# alphanewt_v1_6.net
KiCad netlist of a schematic drawn in EAGLE
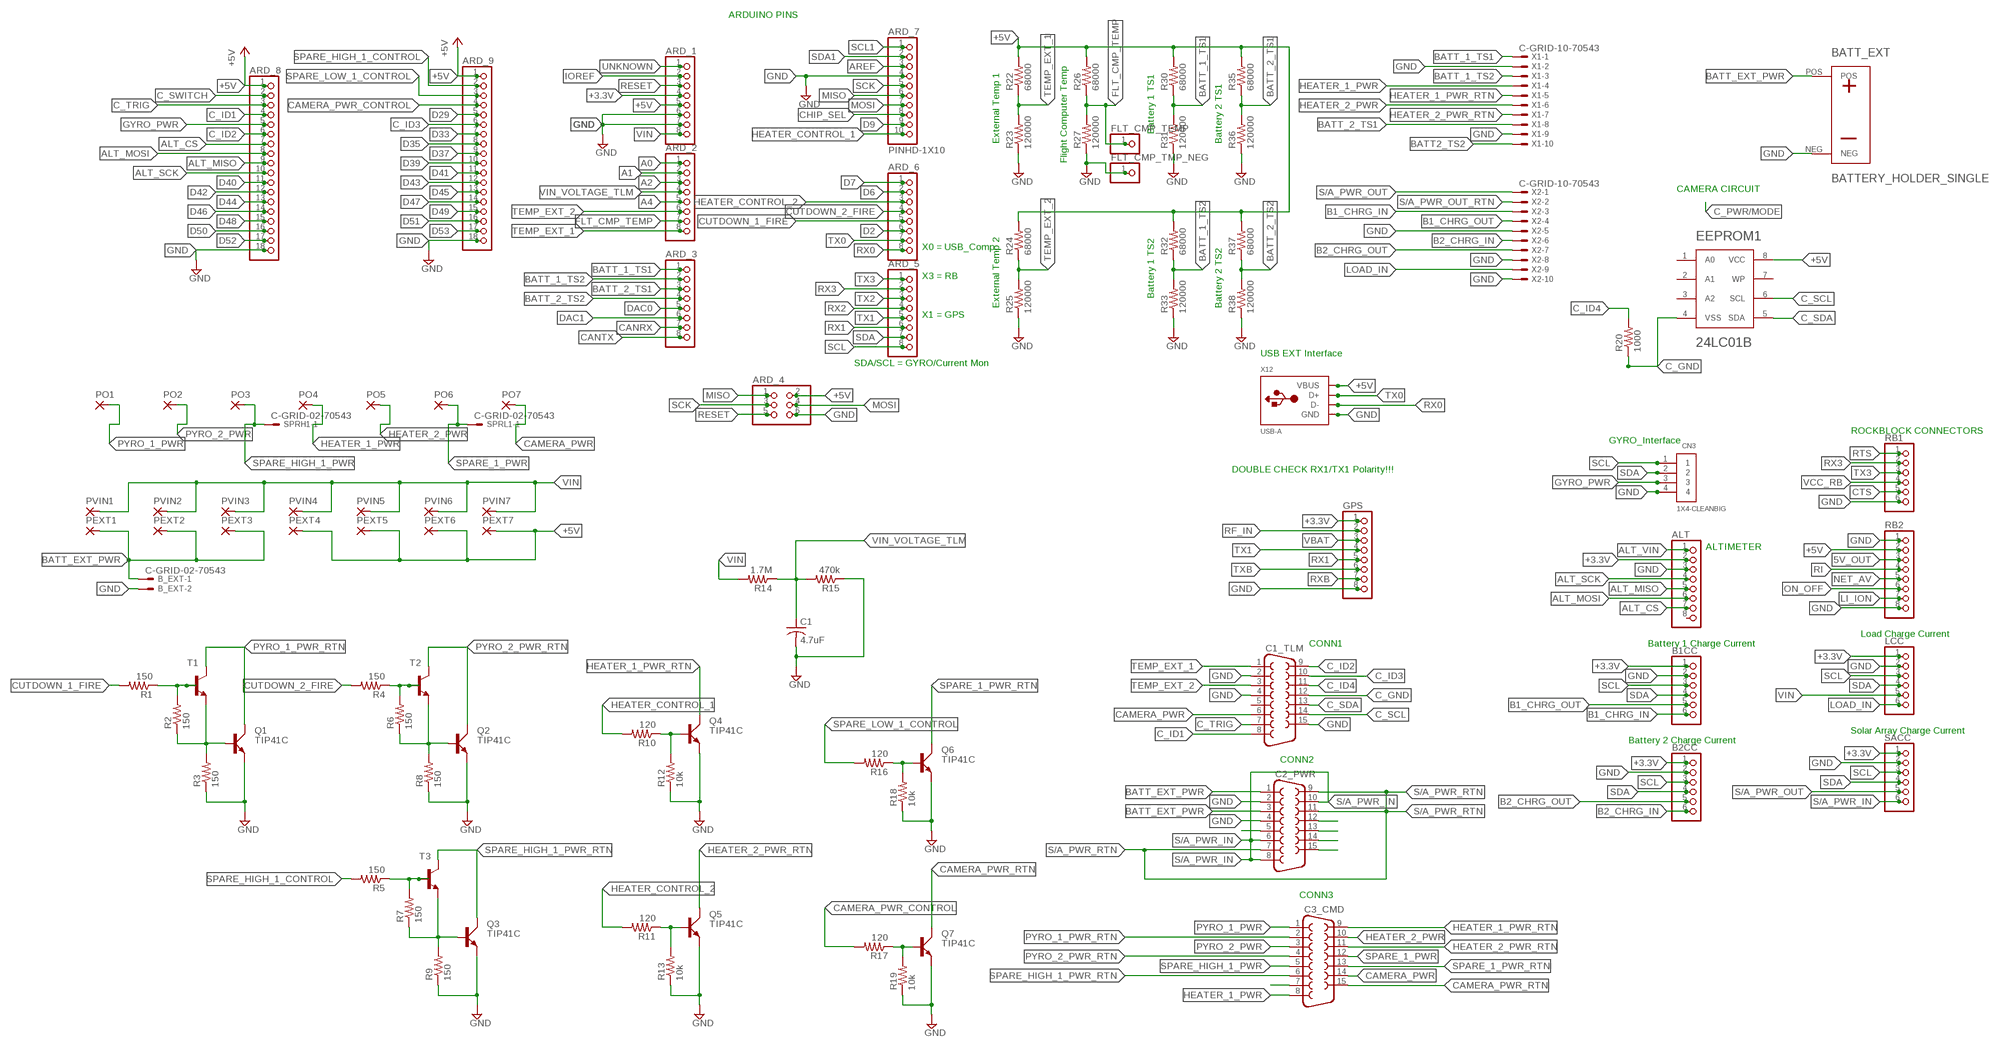
[diagram p0: schematic, sheet 1]

(export (version "E")
  (design (tool "Eeschema 10.0.6"))
  (components
    (comp (ref "ALT")
      (value "PINHD-1X8BIG")
      (footprint "eagle-import:1X08-BIG")
      (libsource (lib "eagle-import") (part "PINHD-1X8BIG"))
    )
    (comp (ref "ARD_1")
      (value "PINHD-1X8BIG")
      (footprint "eagle-import:1X08-BIG")
      (libsource (lib "eagle-import") (part "PINHD-1X8BIG"))
    )
    (comp (ref "ARD_2")
      (value "PINHD-1X8BIG")
      (footprint "eagle-import:1X08-BIG")
      (libsource (lib "eagle-import") (part "PINHD-1X8BIG"))
    )
    (comp (ref "ARD_3")
      (value "PINHD-1X8BIG")
      (footprint "eagle-import:1X08-BIG")
      (libsource (lib "eagle-import") (part "PINHD-1X8BIG"))
    )
    (comp (ref "ARD_4")
      (value "PINHD-2X3")
      (footprint "eagle-import:2X03")
      (libsource (lib "eagle-import") (part "PINHD-2X3"))
    )
    (comp (ref "ARD_5")
      (value "PINHD-1X8BIG")
      (footprint "eagle-import:1X08-BIG")
      (libsource (lib "eagle-import") (part "PINHD-1X8BIG"))
    )
    (comp (ref "ARD_6")
      (value "PINHD-1X8BIG")
      (footprint "eagle-import:1X08-BIG")
      (libsource (lib "eagle-import") (part "PINHD-1X8BIG"))
    )
    (comp (ref "ARD_7")
      (value "PINHD-1X10")
      (footprint "eagle-import:1X10-BIG")
      (libsource (lib "eagle-import") (part "PINHD-1X10"))
    )
    (comp (ref "ARD_8")
      (value "PINHD-1X18-BIG")
      (footprint "eagle-import:1X18-BIG")
      (libsource (lib "eagle-import") (part "PINHD-1X18-BIG"))
    )
    (comp (ref "ARD_9")
      (value "PINHD-1X18-BIG")
      (footprint "eagle-import:1X18-BIG")
      (libsource (lib "eagle-import") (part "PINHD-1X18-BIG"))
    )
    (comp (ref "B1CC")
      (value "PINHD-1X6B")
      (footprint "eagle-import:1X06-BIG")
      (libsource (lib "eagle-import") (part "PINHD-1X6B"))
    )
    (comp (ref "B2CC")
      (value "PINHD-1X6B")
      (footprint "eagle-import:1X06-BIG")
      (libsource (lib "eagle-import") (part "PINHD-1X6B"))
    )
    (comp (ref "BATT_EXT")
      (value "BATTERY_HOLDER_SINGLE")
      (footprint "eagle-import:BATT_HOLDER_SINGLE")
      (libsource (lib "eagle-import") (part "BATTERY_HOLDER_SINGLE"))
    )
    (comp (ref "B_EXT")
      (value "C-GRID-02-70543")
      (footprint "eagle-import:70543-02")
      (fields
        (field (name "MF") "MOLEX")
        (field (name "MPN") "70543-0001")
        (field (name "OC_NEWARK") "59H2645")
      )
      (libsource (lib "eagle-import") (part "C-GRID-02-70543"))
    )
    (comp (ref "C1")
      (value "4.7uF")
      (footprint "eagle-import:C0805K")
      (fields (field (name "MPN") "C2012X6S1H475K125AC"))
      (libsource (lib "eagle-import") (part "C-USC0805K"))
    )
    (comp (ref "C1_TLM")
      (value "F15HP")
      (footprint "eagle-import:F15HP")
      (fields (field (name "MPN") "5504F1-15S-02A-03"))
      (libsource (lib "eagle-import") (part "F15HP"))
    )
    (comp (ref "C2_PWR")
      (value "F15HP")
      (footprint "eagle-import:F15HP")
      (fields (field (name "MPN") "5504F1-15S-02A-03"))
      (libsource (lib "eagle-import") (part "F15HP"))
    )
    (comp (ref "C3_CMD")
      (value "F15HP")
      (footprint "eagle-import:F15HP")
      (fields (field (name "MPN") "5504F1-15S-02A-03"))
      (libsource (lib "eagle-import") (part "F15HP"))
    )
    (comp (ref "CN3")
      (value "1X4-CLEANBIG")
      (footprint "eagle-import:1X04-CLEANBIG")
      (libsource (lib "eagle-import") (part "1X4-CLEANBIG"))
    )
    (comp (ref "EEPROM1")
      (value "24LC01B")
      (footprint "eagle-import:SOP65P490X110-8N")
      (libsource (lib "eagle-import") (part "24LC01B"))
    )
    (comp (ref "FLT_CMP_TEMP")
      (value "PINHD-1X1")
      (footprint "eagle-import:1X01")
      (libsource (lib "eagle-import") (part "PINHD-1X1"))
    )
    (comp (ref "FLT_CMP_TMP_NEG")
      (value "PINHD-1X1")
      (footprint "eagle-import:1X01")
      (libsource (lib "eagle-import") (part "PINHD-1X1"))
    )
    (comp (ref "GPS")
      (value "PINHD-1X8BIG")
      (footprint "eagle-import:1X08-BIG")
      (libsource (lib "eagle-import") (part "PINHD-1X8BIG"))
    )
    (comp (ref "LCC")
      (value "PINHD-1X6B")
      (footprint "eagle-import:1X06-BIG")
      (libsource (lib "eagle-import") (part "PINHD-1X6B"))
    )
    (comp (ref "PEXT1")
      (value "SMD2")
      (footprint "eagle-import:SMD1,27-2,54")
      (libsource (lib "eagle-import") (part "SMD2"))
    )
    (comp (ref "PEXT2")
      (value "SMD2")
      (footprint "eagle-import:SMD1,27-2,54")
      (libsource (lib "eagle-import") (part "SMD2"))
    )
    (comp (ref "PEXT3")
      (value "SMD2")
      (footprint "eagle-import:SMD1,27-2,54")
      (libsource (lib "eagle-import") (part "SMD2"))
    )
    (comp (ref "PEXT4")
      (value "SMD2")
      (footprint "eagle-import:SMD1,27-2,54")
      (libsource (lib "eagle-import") (part "SMD2"))
    )
    (comp (ref "PEXT5")
      (value "SMD2")
      (footprint "eagle-import:SMD1,27-2,54")
      (libsource (lib "eagle-import") (part "SMD2"))
    )
    (comp (ref "PEXT6")
      (value "SMD2")
      (footprint "eagle-import:SMD1,27-2,54")
      (libsource (lib "eagle-import") (part "SMD2"))
    )
    (comp (ref "PEXT7")
      (value "SMD2")
      (footprint "eagle-import:SMD1,27-2,54")
      (libsource (lib "eagle-import") (part "SMD2"))
    )
    (comp (ref "PO1")
      (value "SMD2")
      (footprint "eagle-import:SMD1,27-2,54")
      (libsource (lib "eagle-import") (part "SMD2"))
    )
    (comp (ref "PO2")
      (value "SMD2")
      (footprint "eagle-import:SMD1,27-2,54")
      (libsource (lib "eagle-import") (part "SMD2"))
    )
    (comp (ref "PO3")
      (value "SMD2")
      (footprint "eagle-import:SMD1,27-2,54")
      (libsource (lib "eagle-import") (part "SMD2"))
    )
    (comp (ref "PO4")
      (value "SMD2")
      (footprint "eagle-import:SMD1,27-2,54")
      (libsource (lib "eagle-import") (part "SMD2"))
    )
    (comp (ref "PO5")
      (value "SMD2")
      (footprint "eagle-import:SMD1,27-2,54")
      (libsource (lib "eagle-import") (part "SMD2"))
    )
    (comp (ref "PO6")
      (value "SMD2")
      (footprint "eagle-import:SMD1,27-2,54")
      (libsource (lib "eagle-import") (part "SMD2"))
    )
    (comp (ref "PO7")
      (value "SMD2")
      (footprint "eagle-import:SMD1,27-2,54")
      (libsource (lib "eagle-import") (part "SMD2"))
    )
    (comp (ref "PVIN1")
      (value "SMD2")
      (footprint "eagle-import:SMD1,27-2,54")
      (libsource (lib "eagle-import") (part "SMD2"))
    )
    (comp (ref "PVIN2")
      (value "SMD2")
      (footprint "eagle-import:SMD1,27-2,54")
      (libsource (lib "eagle-import") (part "SMD2"))
    )
    (comp (ref "PVIN3")
      (value "SMD2")
      (footprint "eagle-import:SMD1,27-2,54")
      (libsource (lib "eagle-import") (part "SMD2"))
    )
    (comp (ref "PVIN4")
      (value "SMD2")
      (footprint "eagle-import:SMD1,27-2,54")
      (libsource (lib "eagle-import") (part "SMD2"))
    )
    (comp (ref "PVIN5")
      (value "SMD2")
      (footprint "eagle-import:SMD1,27-2,54")
      (libsource (lib "eagle-import") (part "SMD2"))
    )
    (comp (ref "PVIN6")
      (value "SMD2")
      (footprint "eagle-import:SMD1,27-2,54")
      (libsource (lib "eagle-import") (part "SMD2"))
    )
    (comp (ref "PVIN7")
      (value "SMD2")
      (footprint "eagle-import:SMD1,27-2,54")
      (libsource (lib "eagle-import") (part "SMD2"))
    )
    (comp (ref "Q1")
      (value "TIP41C")
      (footprint "eagle-import:TO220AV")
      (fields (field (name "MF") "FAIRCHILD SEMICONDUCTOR"))
      (libsource (lib "eagle-import") (part "TIP41C"))
    )
    (comp (ref "Q2")
      (value "TIP41C")
      (footprint "eagle-import:TO220AV")
      (fields (field (name "MF") "FAIRCHILD SEMICONDUCTOR"))
      (libsource (lib "eagle-import") (part "TIP41C"))
    )
    (comp (ref "Q3")
      (value "TIP41C")
      (footprint "eagle-import:TO220AV")
      (fields (field (name "MF") "FAIRCHILD SEMICONDUCTOR"))
      (libsource (lib "eagle-import") (part "TIP41C"))
    )
    (comp (ref "Q4")
      (value "TIP41C")
      (footprint "eagle-import:TO220AV")
      (fields (field (name "MF") "FAIRCHILD SEMICONDUCTOR"))
      (libsource (lib "eagle-import") (part "TIP41C"))
    )
    (comp (ref "Q5")
      (value "TIP41C")
      (footprint "eagle-import:TO220AV")
      (fields (field (name "MF") "FAIRCHILD SEMICONDUCTOR"))
      (libsource (lib "eagle-import") (part "TIP41C"))
    )
    (comp (ref "Q6")
      (value "TIP41C")
      (footprint "eagle-import:TO220AV")
      (fields (field (name "MF") "FAIRCHILD SEMICONDUCTOR"))
      (libsource (lib "eagle-import") (part "TIP41C"))
    )
    (comp (ref "Q7")
      (value "TIP41C")
      (footprint "eagle-import:TO220AV")
      (fields (field (name "MF") "FAIRCHILD SEMICONDUCTOR"))
      (libsource (lib "eagle-import") (part "TIP41C"))
    )
    (comp (ref "R1")
      (value "150")
      (footprint "eagle-import:R0805")
      (fields (field (name "MF") "VISHAY/DALE") (field (name "MPN") "CRCW120633R2FKEA"))
      (libsource (lib "eagle-import") (part "R-US_R0805"))
    )
    (comp (ref "R2")
      (value "150")
      (footprint "eagle-import:R0805")
      (fields (field (name "MF") "VISHAY/DALE") (field (name "MPN") "CRCW120633R2FKEA"))
      (libsource (lib "eagle-import") (part "R-US_R0805"))
    )
    (comp (ref "R3")
      (value "150")
      (footprint "eagle-import:R0805")
      (fields (field (name "MF") "VISHAY/DALE") (field (name "MPN") "CRCW120633R2FKEA"))
      (libsource (lib "eagle-import") (part "R-US_R0805"))
    )
    (comp (ref "R4")
      (value "150")
      (footprint "eagle-import:R0805")
      (fields (field (name "MF") "VISHAY/DALE") (field (name "MPN") "CRCW120633R2FKEA"))
      (libsource (lib "eagle-import") (part "R-US_R0805"))
    )
    (comp (ref "R5")
      (value "150")
      (footprint "eagle-import:R0805")
      (fields (field (name "MF") "VISHAY/DALE") (field (name "MPN") "CRCW120633R2FKEA"))
      (libsource (lib "eagle-import") (part "R-US_R0805"))
    )
    (comp (ref "R6")
      (value "150")
      (footprint "eagle-import:R0805")
      (fields (field (name "MF") "VISHAY/DALE") (field (name "MPN") "CRCW120633R2FKEA"))
      (libsource (lib "eagle-import") (part "R-US_R0805"))
    )
    (comp (ref "R7")
      (value "150")
      (footprint "eagle-import:R0805")
      (fields (field (name "MF") "VISHAY/DALE") (field (name "MPN") "CRCW120633R2FKEA"))
      (libsource (lib "eagle-import") (part "R-US_R0805"))
    )
    (comp (ref "R8")
      (value "150")
      (footprint "eagle-import:R0805")
      (fields (field (name "MF") "VISHAY/DALE") (field (name "MPN") "CRCW120633R2FKEA"))
      (libsource (lib "eagle-import") (part "R-US_R0805"))
    )
    (comp (ref "R9")
      (value "150")
      (footprint "eagle-import:R0805")
      (fields (field (name "MF") "VISHAY/DALE") (field (name "MPN") "CRCW120633R2FKEA"))
      (libsource (lib "eagle-import") (part "R-US_R0805"))
    )
    (comp (ref "R10")
      (value "120")
      (footprint "eagle-import:R0805")
      (fields (field (name "MF") "VISHAY/DALE") (field (name "MPN") "CRCW120633R2FKEA"))
      (libsource (lib "eagle-import") (part "R-US_R0805"))
    )
    (comp (ref "R11")
      (value "120")
      (footprint "eagle-import:R0805")
      (fields (field (name "MF") "VISHAY/DALE") (field (name "MPN") "CRCW120633R2FKEA"))
      (libsource (lib "eagle-import") (part "R-US_R0805"))
    )
    (comp (ref "R12")
      (value "10k")
      (footprint "eagle-import:R0805")
      (fields (field (name "MF") "VISHAY/DALE") (field (name "MPN") "CRCW120633R2FKEA"))
      (libsource (lib "eagle-import") (part "R-US_R0805"))
    )
    (comp (ref "R13")
      (value "10k")
      (footprint "eagle-import:R0805")
      (fields (field (name "MF") "VISHAY/DALE") (field (name "MPN") "CRCW120633R2FKEA"))
      (libsource (lib "eagle-import") (part "R-US_R0805"))
    )
    (comp (ref "R14")
      (value "1.7M")
      (footprint "eagle-import:R0805")
      (fields (field (name "MF") "VISHAY/DALE") (field (name "MPN") "CRCW120633R2FKEA"))
      (libsource (lib "eagle-import") (part "R-US_R0805"))
    )
    (comp (ref "R15")
      (value "470k")
      (footprint "eagle-import:R0805")
      (fields (field (name "MF") "VISHAY/DALE") (field (name "MPN") "CRCW120633R2FKEA"))
      (libsource (lib "eagle-import") (part "R-US_R0805"))
    )
    (comp (ref "R16")
      (value "120")
      (footprint "eagle-import:R0805")
      (fields (field (name "MF") "VISHAY/DALE") (field (name "MPN") "CRCW120633R2FKEA"))
      (libsource (lib "eagle-import") (part "R-US_R0805"))
    )
    (comp (ref "R17")
      (value "120")
      (footprint "eagle-import:R0805")
      (fields (field (name "MF") "VISHAY/DALE") (field (name "MPN") "CRCW120633R2FKEA"))
      (libsource (lib "eagle-import") (part "R-US_R0805"))
    )
    (comp (ref "R18")
      (value "10k")
      (footprint "eagle-import:R0805")
      (fields (field (name "MF") "VISHAY/DALE") (field (name "MPN") "CRCW120633R2FKEA"))
      (libsource (lib "eagle-import") (part "R-US_R0805"))
    )
    (comp (ref "R19")
      (value "10k")
      (footprint "eagle-import:R0805")
      (fields (field (name "MF") "VISHAY/DALE") (field (name "MPN") "CRCW120633R2FKEA"))
      (libsource (lib "eagle-import") (part "R-US_R0805"))
    )
    (comp (ref "R20")
      (value "1000")
      (footprint "eagle-import:R0805")
      (fields (field (name "MF") "VISHAY/DALE") (field (name "MPN") "CRCW120633R2FKEA"))
      (libsource (lib "eagle-import") (part "R-US_R0805"))
    )
    (comp (ref "R22")
      (value "68000")
      (footprint "eagle-import:R0805")
      (fields (field (name "MF") "VISHAY/DALE") (field (name "MPN") "CRCW120633R2FKEA"))
      (libsource (lib "eagle-import") (part "R-US_R0805"))
    )
    (comp (ref "R23")
      (value "120000")
      (footprint "eagle-import:R0805")
      (fields (field (name "MF") "VISHAY/DALE") (field (name "MPN") "CRCW120633R2FKEA"))
      (libsource (lib "eagle-import") (part "R-US_R0805"))
    )
    (comp (ref "R24")
      (value "68000")
      (footprint "eagle-import:R0805")
      (fields (field (name "MF") "VISHAY/DALE") (field (name "MPN") "CRCW120633R2FKEA"))
      (libsource (lib "eagle-import") (part "R-US_R0805"))
    )
    (comp (ref "R25")
      (value "120000")
      (footprint "eagle-import:R0805")
      (fields (field (name "MF") "VISHAY/DALE") (field (name "MPN") "CRCW120633R2FKEA"))
      (libsource (lib "eagle-import") (part "R-US_R0805"))
    )
    (comp (ref "R26")
      (value "68000")
      (footprint "eagle-import:R0805")
      (fields (field (name "MF") "VISHAY/DALE") (field (name "MPN") "CRCW120633R2FKEA"))
      (libsource (lib "eagle-import") (part "R-US_R0805"))
    )
    (comp (ref "R27")
      (value "120000")
      (footprint "eagle-import:R0805")
      (fields (field (name "MF") "VISHAY/DALE") (field (name "MPN") "CRCW120633R2FKEA"))
      (libsource (lib "eagle-import") (part "R-US_R0805"))
    )
    (comp (ref "R30")
      (value "68000")
      (footprint "eagle-import:R0805")
      (fields (field (name "MF") "VISHAY/DALE") (field (name "MPN") "CRCW120633R2FKEA"))
      (libsource (lib "eagle-import") (part "R-US_R0805"))
    )
    (comp (ref "R31")
      (value "120000")
      (footprint "eagle-import:R0805")
      (fields (field (name "MF") "VISHAY/DALE") (field (name "MPN") "CRCW120633R2FKEA"))
      (libsource (lib "eagle-import") (part "R-US_R0805"))
    )
    (comp (ref "R32")
      (value "68000")
      (footprint "eagle-import:R0805")
      (fields (field (name "MF") "VISHAY/DALE") (field (name "MPN") "CRCW120633R2FKEA"))
      (libsource (lib "eagle-import") (part "R-US_R0805"))
    )
    (comp (ref "R33")
      (value "120000")
      (footprint "eagle-import:R0805")
      (fields (field (name "MF") "VISHAY/DALE") (field (name "MPN") "CRCW120633R2FKEA"))
      (libsource (lib "eagle-import") (part "R-US_R0805"))
    )
    (comp (ref "R35")
      (value "68000")
      (footprint "eagle-import:R0805")
      (fields (field (name "MF") "VISHAY/DALE") (field (name "MPN") "CRCW120633R2FKEA"))
      (libsource (lib "eagle-import") (part "R-US_R0805"))
    )
    (comp (ref "R36")
      (value "120000")
      (footprint "eagle-import:R0805")
      (fields (field (name "MF") "VISHAY/DALE") (field (name "MPN") "CRCW120633R2FKEA"))
      (libsource (lib "eagle-import") (part "R-US_R0805"))
    )
    (comp (ref "R37")
      (value "68000")
      (footprint "eagle-import:R0805")
      (fields (field (name "MF") "VISHAY/DALE") (field (name "MPN") "CRCW120633R2FKEA"))
      (libsource (lib "eagle-import") (part "R-US_R0805"))
    )
    (comp (ref "R38")
      (value "120000")
      (footprint "eagle-import:R0805")
      (fields (field (name "MF") "VISHAY/DALE") (field (name "MPN") "CRCW120633R2FKEA"))
      (libsource (lib "eagle-import") (part "R-US_R0805"))
    )
    (comp (ref "RB1")
      (value "PINHD-1X6CB")
      (footprint "eagle-import:1X06-CLEANBIG")
      (libsource (lib "eagle-import") (part "PINHD-1X6CB"))
    )
    (comp (ref "RB2")
      (value "PINHD-1X8BIG")
      (footprint "eagle-import:1X08-BIG")
      (libsource (lib "eagle-import") (part "PINHD-1X8BIG"))
    )
    (comp (ref "SACC")
      (value "PINHD-1X6B")
      (footprint "eagle-import:1X06-BIG")
      (libsource (lib "eagle-import") (part "PINHD-1X6B"))
    )
    (comp (ref "SPRH1")
      (value "C-GRID-02-70543")
      (footprint "eagle-import:70543-02")
      (fields
        (field (name "MF") "MOLEX")
        (field (name "MPN") "70543-0001")
        (field (name "OC_NEWARK") "59H2645")
      )
      (libsource (lib "eagle-import") (part "C-GRID-02-70543"))
    )
    (comp (ref "SPRL1")
      (value "C-GRID-02-70543")
      (footprint "eagle-import:70543-02")
      (fields
        (field (name "MF") "MOLEX")
        (field (name "MPN") "70543-0001")
        (field (name "OC_NEWARK") "59H2645")
      )
      (libsource (lib "eagle-import") (part "C-GRID-02-70543"))
    )
    (comp (ref "T1")
      (value "2N3904")
      (footprint "eagle-import:TO92")
      (fields (field (name "MF") "NTE ELECTRONICS"))
      (libsource (lib "eagle-import") (part "2N3904"))
    )
    (comp (ref "T2")
      (value "2N3904")
      (footprint "eagle-import:TO92")
      (fields (field (name "MF") "NTE ELECTRONICS"))
      (libsource (lib "eagle-import") (part "2N3904"))
    )
    (comp (ref "T3")
      (value "2N3904")
      (footprint "eagle-import:TO92")
      (fields (field (name "MF") "NTE ELECTRONICS"))
      (libsource (lib "eagle-import") (part "2N3904"))
    )
    (comp (ref "X1")
      (value "C-GRID-10-70543")
      (footprint "eagle-import:70543-10")
      (libsource (lib "eagle-import") (part "C-GRID-10-70543"))
    )
    (comp (ref "X2")
      (value "C-GRID-10-70543")
      (footprint "eagle-import:70543-10")
      (libsource (lib "eagle-import") (part "C-GRID-10-70543"))
    )
    (comp (ref "X12")
      (value "USB-A")
      (footprint "eagle-import:MOLEX_480371000")
      (fields (field (name "MPN") "UE27-AC54-10H"))
      (libsource (lib "eagle-import") (part "USB-A"))
    )
  )
  (nets
    (net (code "1") (name "+3.3V") (class "Default")
      (node (ref "ALT") (pin "2") (pinfunction "2_2") (pintype "passive"))
      (node (ref "ARD_1") (pin "4") (pinfunction "4_4") (pintype "passive"))
      (node (ref "B1CC") (pin "1") (pinfunction "1_1") (pintype "passive"))
      (node (ref "B2CC") (pin "1") (pinfunction "1_1") (pintype "passive"))
      (node (ref "GPS") (pin "1") (pinfunction "1_1") (pintype "passive"))
      (node (ref "LCC") (pin "1") (pinfunction "1_1") (pintype "passive"))
      (node (ref "SACC") (pin "1") (pinfunction "1_1") (pintype "passive"))
    )
    (net (code "2") (name "+5V") (class "Default")
      (node (ref "ARD_1") (pin "5") (pinfunction "5_5") (pintype "passive"))
      (node (ref "ARD_4") (pin "2") (pinfunction "2_2") (pintype "passive"))
      (node (ref "ARD_8") (pin "1") (pinfunction "1_1") (pintype "passive"))
      (node (ref "ARD_9") (pin "1") (pinfunction "1_1") (pintype "passive"))
      (node (ref "EEPROM1") (pin "8") (pinfunction "VCC_8") (pintype "bidirectional"))
      (node (ref "PEXT4") (pin "1") (pinfunction "P_1") (pintype "passive"))
      (node (ref "PEXT5") (pin "1") (pinfunction "P_1") (pintype "passive"))
      (node (ref "PEXT6") (pin "1") (pinfunction "P_1") (pintype "passive"))
      (node (ref "PEXT7") (pin "1") (pinfunction "P_1") (pintype "passive"))
      (node (ref "R22") (pin "2") (pinfunction "2_2") (pintype "passive"))
      (node (ref "R24") (pin "2") (pinfunction "2_2") (pintype "passive"))
      (node (ref "R26") (pin "2") (pinfunction "2_2") (pintype "passive"))
      (node (ref "R30") (pin "2") (pinfunction "2_2") (pintype "passive"))
      (node (ref "R32") (pin "2") (pinfunction "2_2") (pintype "passive"))
      (node (ref "R35") (pin "2") (pinfunction "2_2") (pintype "passive"))
      (node (ref "R37") (pin "2") (pinfunction "2_2") (pintype "passive"))
      (node (ref "RB2") (pin "2") (pinfunction "2_2") (pintype "passive"))
      (node (ref "X12") (pin "1") (pinfunction "VBUS_1") (pintype "power_in"))
    )
    (net (code "3") (name "5V_OUT") (class "Default")
      (node (ref "RB2") (pin "3") (pinfunction "3_3") (pintype "passive"))
    )
    (net (code "4") (name "A0") (class "Default")
      (node (ref "ARD_2") (pin "1") (pinfunction "1_1") (pintype "passive"))
    )
    (net (code "5") (name "A1") (class "Default")
      (node (ref "ARD_2") (pin "2") (pinfunction "2_2") (pintype "passive"))
    )
    (net (code "6") (name "A2") (class "Default")
      (node (ref "ARD_2") (pin "3") (pinfunction "3_3") (pintype "passive"))
    )
    (net (code "7") (name "A4") (class "Default")
      (node (ref "ARD_2") (pin "5") (pinfunction "5_5") (pintype "passive"))
    )
    (net (code "8") (name "ALT_CS") (class "Default")
      (node (ref "ALT") (pin "7") (pinfunction "7_7") (pintype "passive"))
      (node (ref "ARD_8") (pin "7") (pinfunction "7_7") (pintype "passive"))
    )
    (net (code "9") (name "ALT_MISO") (class "Default")
      (node (ref "ALT") (pin "5") (pinfunction "5_5") (pintype "passive"))
      (node (ref "ARD_8") (pin "9") (pinfunction "9_9") (pintype "passive"))
    )
    (net (code "10") (name "ALT_MOSI") (class "Default")
      (node (ref "ALT") (pin "6") (pinfunction "6_6") (pintype "passive"))
      (node (ref "ARD_8") (pin "8") (pinfunction "8_8") (pintype "passive"))
    )
    (net (code "11") (name "ALT_SCK") (class "Default")
      (node (ref "ALT") (pin "4") (pinfunction "4_4") (pintype "passive"))
      (node (ref "ARD_8") (pin "10") (pinfunction "10_10") (pintype "passive"))
    )
    (net (code "12") (name "ALT_VIN") (class "Default")
      (node (ref "ALT") (pin "1") (pinfunction "1_1") (pintype "passive"))
    )
    (net (code "13") (name "AREF") (class "Default")
      (node (ref "ARD_7") (pin "3") (pinfunction "3_3") (pintype "passive"))
    )
    (net (code "14") (name "B1_CHRG_IN") (class "Default")
      (node (ref "B1CC") (pin "6") (pinfunction "6_6") (pintype "passive"))
      (node (ref "X2") (pin "3") (pinfunction "S_3") (pintype "passive"))
    )
    (net (code "15") (name "B1_CHRG_OUT") (class "Default")
      (node (ref "B1CC") (pin "5") (pinfunction "5_5") (pintype "passive"))
      (node (ref "X2") (pin "4") (pinfunction "S_4") (pintype "passive"))
    )
    (net (code "16") (name "B2_CHRG_IN") (class "Default")
      (node (ref "B2CC") (pin "6") (pinfunction "6_6") (pintype "passive"))
      (node (ref "X2") (pin "6") (pinfunction "S_6") (pintype "passive"))
    )
    (net (code "17") (name "B2_CHRG_OUT") (class "Default")
      (node (ref "B2CC") (pin "5") (pinfunction "5_5") (pintype "passive"))
      (node (ref "X2") (pin "7") (pinfunction "S_7") (pintype "passive"))
    )
    (net (code "18") (name "BATT2_TS2") (class "Default")
      (node (ref "X1") (pin "10") (pinfunction "S_10") (pintype "passive"))
    )
    (net (code "19") (name "BATT_1_TS1") (class "Default")
      (node (ref "ARD_3") (pin "1") (pinfunction "1_1") (pintype "passive"))
      (node (ref "R30") (pin "1") (pinfunction "1_1") (pintype "passive"))
      (node (ref "R31") (pin "2") (pinfunction "2_2") (pintype "passive"))
      (node (ref "X1") (pin "1") (pinfunction "S_1") (pintype "passive"))
    )
    (net (code "20") (name "BATT_1_TS2") (class "Default")
      (node (ref "ARD_3") (pin "2") (pinfunction "2_2") (pintype "passive"))
      (node (ref "R32") (pin "1") (pinfunction "1_1") (pintype "passive"))
      (node (ref "R33") (pin "2") (pinfunction "2_2") (pintype "passive"))
      (node (ref "X1") (pin "3") (pinfunction "S_3") (pintype "passive"))
    )
    (net (code "21") (name "BATT_2_TS1") (class "Default")
      (node (ref "ARD_3") (pin "3") (pinfunction "3_3") (pintype "passive"))
      (node (ref "R35") (pin "1") (pinfunction "1_1") (pintype "passive"))
      (node (ref "R36") (pin "2") (pinfunction "2_2") (pintype "passive"))
      (node (ref "X1") (pin "8") (pinfunction "S_8") (pintype "passive"))
    )
    (net (code "22") (name "BATT_2_TS2") (class "Default")
      (node (ref "ARD_3") (pin "4") (pinfunction "4_4") (pintype "passive"))
      (node (ref "R37") (pin "1") (pinfunction "1_1") (pintype "passive"))
      (node (ref "R38") (pin "2") (pinfunction "2_2") (pintype "passive"))
    )
    (net (code "23") (name "BATT_EXT_PWR") (class "Default")
      (node (ref "BATT_EXT") (pin "POS") (pinfunction "POS_POS") (pintype "bidirectional"))
      (node (ref "B_EXT") (pin "1") (pinfunction "S_1") (pintype "passive"))
      (node (ref "C2_PWR") (pin "1") (pinfunction "1_1") (pintype "passive"))
      (node (ref "C2_PWR") (pin "3") (pinfunction "3_3") (pintype "passive"))
      (node (ref "PEXT1") (pin "1") (pinfunction "P_1") (pintype "passive"))
      (node (ref "PEXT2") (pin "1") (pinfunction "P_1") (pintype "passive"))
      (node (ref "PEXT3") (pin "1") (pinfunction "P_1") (pintype "passive"))
    )
    (net (code "24") (name "CAMERA_PWR") (class "Default")
      (node (ref "C1_TLM") (pin "6") (pinfunction "6_6") (pintype "passive"))
      (node (ref "C3_CMD") (pin "14") (pinfunction "14_14") (pintype "passive"))
      (node (ref "PO7") (pin "1") (pinfunction "P_1") (pintype "passive"))
    )
    (net (code "25") (name "CAMERA_PWR_CONTROL") (class "Default")
      (node (ref "ARD_9") (pin "4") (pinfunction "4_4") (pintype "passive"))
      (node (ref "R17") (pin "2") (pinfunction "2_2") (pintype "passive"))
    )
    (net (code "26") (name "CAMERA_PWR_RTN") (class "Default")
      (node (ref "C3_CMD") (pin "15") (pinfunction "15_15") (pintype "passive"))
      (node (ref "Q7") (pin "C") (pinfunction "C_C") (pintype "passive"))
    )
    (net (code "27") (name "CANRX") (class "Default")
      (node (ref "ARD_3") (pin "7") (pinfunction "7_7") (pintype "passive"))
    )
    (net (code "28") (name "CANTX") (class "Default")
      (node (ref "ARD_3") (pin "8") (pinfunction "8_8") (pintype "passive"))
    )
    (net (code "29") (name "CHIP_SEL") (class "Default")
      (node (ref "ARD_7") (pin "8") (pinfunction "8_8") (pintype "passive"))
    )
    (net (code "30") (name "CTS") (class "Default")
      (node (ref "RB1") (pin "5") (pinfunction "5_5") (pintype "passive"))
    )
    (net (code "31") (name "CUTDOWN_1_FIRE") (class "Default")
      (node (ref "ARD_6") (pin "5") (pinfunction "5_5") (pintype "passive"))
      (node (ref "R1") (pin "2") (pinfunction "2_2") (pintype "passive"))
    )
    (net (code "32") (name "CUTDOWN_2_FIRE") (class "Default")
      (node (ref "ARD_6") (pin "4") (pinfunction "4_4") (pintype "passive"))
      (node (ref "R4") (pin "2") (pinfunction "2_2") (pintype "passive"))
    )
    (net (code "33") (name "C_GND") (class "Default")
      (node (ref "C1_TLM") (pin "12") (pinfunction "12_12") (pintype "passive"))
      (node (ref "EEPROM1") (pin "4") (pinfunction "VSS_4") (pintype "bidirectional"))
      (node (ref "R20") (pin "1") (pinfunction "1_1") (pintype "passive"))
    )
    (net (code "34") (name "C_ID1") (class "Default")
      (node (ref "ARD_8") (pin "4") (pinfunction "4_4") (pintype "passive"))
      (node (ref "C1_TLM") (pin "8") (pinfunction "8_8") (pintype "passive"))
    )
    (net (code "35") (name "C_ID2") (class "Default")
      (node (ref "ARD_8") (pin "6") (pinfunction "6_6") (pintype "passive"))
      (node (ref "C1_TLM") (pin "9") (pinfunction "9_9") (pintype "passive"))
    )
    (net (code "36") (name "C_ID3") (class "Default")
      (node (ref "ARD_9") (pin "6") (pinfunction "6_6") (pintype "passive"))
      (node (ref "C1_TLM") (pin "10") (pinfunction "10_10") (pintype "passive"))
    )
    (net (code "37") (name "C_ID4") (class "Default")
      (node (ref "C1_TLM") (pin "11") (pinfunction "11_11") (pintype "passive"))
      (node (ref "R20") (pin "2") (pinfunction "2_2") (pintype "passive"))
    )
    (net (code "39") (name "C_SCL") (class "Default")
      (node (ref "C1_TLM") (pin "14") (pinfunction "14_14") (pintype "passive"))
      (node (ref "EEPROM1") (pin "6") (pinfunction "SCL_6") (pintype "bidirectional"))
    )
    (net (code "40") (name "C_SDA") (class "Default")
      (node (ref "C1_TLM") (pin "13") (pinfunction "13_13") (pintype "passive"))
      (node (ref "EEPROM1") (pin "5") (pinfunction "SDA_5") (pintype "bidirectional"))
    )
    (net (code "41") (name "C_SWITCH") (class "Default")
      (node (ref "ARD_8") (pin "2") (pinfunction "2_2") (pintype "passive"))
    )
    (net (code "42") (name "C_TRIG") (class "Default")
      (node (ref "ARD_8") (pin "3") (pinfunction "3_3") (pintype "passive"))
      (node (ref "C1_TLM") (pin "7") (pinfunction "7_7") (pintype "passive"))
    )
    (net (code "43") (name "D2") (class "Default")
      (node (ref "ARD_6") (pin "6") (pinfunction "6_6") (pintype "passive"))
    )
    (net (code "44") (name "D6") (class "Default")
      (node (ref "ARD_6") (pin "2") (pinfunction "2_2") (pintype "passive"))
    )
    (net (code "45") (name "D7") (class "Default")
      (node (ref "ARD_6") (pin "1") (pinfunction "1_1") (pintype "passive"))
    )
    (net (code "46") (name "D9") (class "Default")
      (node (ref "ARD_7") (pin "9") (pinfunction "9_9") (pintype "passive"))
    )
    (net (code "47") (name "D29") (class "Default")
      (node (ref "ARD_9") (pin "5") (pinfunction "5_5") (pintype "passive"))
    )
    (net (code "48") (name "D33") (class "Default")
      (node (ref "ARD_9") (pin "7") (pinfunction "7_7") (pintype "passive"))
    )
    (net (code "49") (name "D35") (class "Default")
      (node (ref "ARD_9") (pin "8") (pinfunction "8_8") (pintype "passive"))
    )
    (net (code "50") (name "D37") (class "Default")
      (node (ref "ARD_9") (pin "9") (pinfunction "9_9") (pintype "passive"))
    )
    (net (code "51") (name "D39") (class "Default")
      (node (ref "ARD_9") (pin "10") (pinfunction "10_10") (pintype "passive"))
    )
    (net (code "52") (name "D40") (class "Default")
      (node (ref "ARD_8") (pin "11") (pinfunction "11_11") (pintype "passive"))
    )
    (net (code "53") (name "D41") (class "Default")
      (node (ref "ARD_9") (pin "11") (pinfunction "11_11") (pintype "passive"))
    )
    (net (code "54") (name "D42") (class "Default")
      (node (ref "ARD_8") (pin "12") (pinfunction "12_12") (pintype "passive"))
    )
    (net (code "55") (name "D43") (class "Default")
      (node (ref "ARD_9") (pin "12") (pinfunction "12_12") (pintype "passive"))
    )
    (net (code "56") (name "D44") (class "Default")
      (node (ref "ARD_8") (pin "13") (pinfunction "13_13") (pintype "passive"))
    )
    (net (code "57") (name "D45") (class "Default")
      (node (ref "ARD_9") (pin "13") (pinfunction "13_13") (pintype "passive"))
    )
    (net (code "58") (name "D46") (class "Default")
      (node (ref "ARD_8") (pin "14") (pinfunction "14_14") (pintype "passive"))
    )
    (net (code "59") (name "D47") (class "Default")
      (node (ref "ARD_9") (pin "14") (pinfunction "14_14") (pintype "passive"))
    )
    (net (code "60") (name "D48") (class "Default")
      (node (ref "ARD_8") (pin "15") (pinfunction "15_15") (pintype "passive"))
    )
    (net (code "61") (name "D49") (class "Default")
      (node (ref "ARD_9") (pin "15") (pinfunction "15_15") (pintype "passive"))
    )
    (net (code "62") (name "D50") (class "Default")
      (node (ref "ARD_8") (pin "16") (pinfunction "16_16") (pintype "passive"))
    )
    (net (code "63") (name "D51") (class "Default")
      (node (ref "ARD_9") (pin "16") (pinfunction "16_16") (pintype "passive"))
    )
    (net (code "64") (name "D52") (class "Default")
      (node (ref "ARD_8") (pin "17") (pinfunction "17_17") (pintype "passive"))
    )
    (net (code "65") (name "D53") (class "Default")
      (node (ref "ARD_9") (pin "17") (pinfunction "17_17") (pintype "passive"))
    )
    (net (code "66") (name "DAC0") (class "Default")
      (node (ref "ARD_3") (pin "5") (pinfunction "5_5") (pintype "passive"))
    )
    (net (code "67") (name "DAC1") (class "Default")
      (node (ref "ARD_3") (pin "6") (pinfunction "6_6") (pintype "passive"))
    )
    (net (code "68") (name "FLT_CMP_TEMP") (class "Default")
      (node (ref "ARD_2") (pin "7") (pinfunction "7_7") (pintype "passive"))
      (node (ref "FLT_CMP_TEMP") (pin "1") (pinfunction "1_1") (pintype "passive"))
      (node (ref "R26") (pin "1") (pinfunction "1_1") (pintype "passive"))
      (node (ref "R27") (pin "2") (pinfunction "2_2") (pintype "passive"))
    )
    (net (code "69") (name "GND") (class "Default")
      (node (ref "ALT") (pin "3") (pinfunction "3_3") (pintype "passive"))
      (node (ref "ARD_1") (pin "6") (pinfunction "6_6") (pintype "passive"))
      (node (ref "ARD_1") (pin "7") (pinfunction "7_7") (pintype "passive"))
      (node (ref "ARD_4") (pin "6") (pinfunction "6_6") (pintype "passive"))
      (node (ref "ARD_7") (pin "4") (pinfunction "4_4") (pintype "passive"))
      (node (ref "ARD_8") (pin "18") (pinfunction "18_18") (pintype "passive"))
      (node (ref "ARD_9") (pin "18") (pinfunction "18_18") (pintype "passive"))
      (node (ref "B1CC") (pin "2") (pinfunction "2_2") (pintype "passive"))
      (node (ref "B2CC") (pin "2") (pinfunction "2_2") (pintype "passive"))
      (node (ref "BATT_EXT") (pin "NEG") (pinfunction "NEG_NEG") (pintype "bidirectional"))
      (node (ref "B_EXT") (pin "2") (pinfunction "S_2") (pintype "passive"))
      (node (ref "C1") (pin "2") (pinfunction "2_2") (pintype "passive"))
      (node (ref "C1_TLM") (pin "15") (pinfunction "15_15") (pintype "passive"))
      (node (ref "C1_TLM") (pin "2") (pinfunction "2_2") (pintype "passive"))
      (node (ref "C1_TLM") (pin "4") (pinfunction "4_4") (pintype "passive"))
      (node (ref "C2_PWR") (pin "2") (pinfunction "2_2") (pintype "passive"))
      (node (ref "C2_PWR") (pin "4") (pinfunction "4_4") (pintype "passive"))
      (node (ref "CN3") (pin "4") (pinfunction "4_4") (pintype "bidirectional"))
      (node (ref "FLT_CMP_TMP_NEG") (pin "1") (pinfunction "1_1") (pintype "passive"))
      (node (ref "GPS") (pin "8") (pinfunction "8_8") (pintype "passive"))
      (node (ref "LCC") (pin "2") (pinfunction "2_2") (pintype "passive"))
      (node (ref "Q1") (pin "E") (pinfunction "E_E") (pintype "passive"))
      (node (ref "Q2") (pin "E") (pinfunction "E_E") (pintype "passive"))
      (node (ref "Q3") (pin "E") (pinfunction "E_E") (pintype "passive"))
      (node (ref "Q4") (pin "E") (pinfunction "E_E") (pintype "passive"))
      (node (ref "Q5") (pin "E") (pinfunction "E_E") (pintype "passive"))
      (node (ref "Q6") (pin "E") (pinfunction "E_E") (pintype "passive"))
      (node (ref "Q7") (pin "E") (pinfunction "E_E") (pintype "passive"))
      (node (ref "R12") (pin "1") (pinfunction "1_1") (pintype "passive"))
      (node (ref "R13") (pin "1") (pinfunction "1_1") (pintype "passive"))
      (node (ref "R15") (pin "1") (pinfunction "1_1") (pintype "passive"))
      (node (ref "R18") (pin "1") (pinfunction "1_1") (pintype "passive"))
      (node (ref "R19") (pin "1") (pinfunction "1_1") (pintype "passive"))
      (node (ref "R23") (pin "1") (pinfunction "1_1") (pintype "passive"))
      (node (ref "R25") (pin "1") (pinfunction "1_1") (pintype "passive"))
      (node (ref "R27") (pin "1") (pinfunction "1_1") (pintype "passive"))
      (node (ref "R3") (pin "1") (pinfunction "1_1") (pintype "passive"))
      (node (ref "R31") (pin "1") (pinfunction "1_1") (pintype "passive"))
      (node (ref "R33") (pin "1") (pinfunction "1_1") (pintype "passive"))
      (node (ref "R36") (pin "1") (pinfunction "1_1") (pintype "passive"))
      (node (ref "R38") (pin "1") (pinfunction "1_1") (pintype "passive"))
      (node (ref "R8") (pin "1") (pinfunction "1_1") (pintype "passive"))
      (node (ref "R9") (pin "1") (pinfunction "1_1") (pintype "passive"))
      (node (ref "RB1") (pin "6") (pinfunction "6_6") (pintype "passive"))
      (node (ref "RB2") (pin "1") (pinfunction "1_1") (pintype "passive"))
      (node (ref "RB2") (pin "8") (pinfunction "8_8") (pintype "passive"))
      (node (ref "SACC") (pin "2") (pinfunction "2_2") (pintype "passive"))
      (node (ref "X1") (pin "2") (pinfunction "S_2") (pintype "passive"))
      (node (ref "X1") (pin "9") (pinfunction "S_9") (pintype "passive"))
      (node (ref "X12") (pin "4") (pinfunction "GND_4") (pintype "power_in"))
      (node (ref "X2") (pin "10") (pinfunction "S_10") (pintype "passive"))
      (node (ref "X2") (pin "5") (pinfunction "S_5") (pintype "passive"))
      (node (ref "X2") (pin "8") (pinfunction "S_8") (pintype "passive"))
    )
    (net (code "70") (name "GYRO_PWR") (class "Default")
      (node (ref "ARD_8") (pin "5") (pinfunction "5_5") (pintype "passive"))
      (node (ref "CN3") (pin "3") (pinfunction "3_3") (pintype "bidirectional"))
    )
    (net (code "71") (name "HEATER_1_PWR") (class "Default")
      (node (ref "C3_CMD") (pin "8") (pinfunction "8_8") (pintype "passive"))
      (node (ref "PO4") (pin "1") (pinfunction "P_1") (pintype "passive"))
      (node (ref "X1") (pin "4") (pinfunction "S_4") (pintype "passive"))
    )
    (net (code "72") (name "HEATER_1_PWR_RTN") (class "Default")
      (node (ref "C3_CMD") (pin "9") (pinfunction "9_9") (pintype "passive"))
      (node (ref "Q4") (pin "C") (pinfunction "C_C") (pintype "passive"))
      (node (ref "X1") (pin "5") (pinfunction "S_5") (pintype "passive"))
    )
    (net (code "73") (name "HEATER_2_PWR") (class "Default")
      (node (ref "C3_CMD") (pin "10") (pinfunction "10_10") (pintype "passive"))
      (node (ref "PO5") (pin "1") (pinfunction "P_1") (pintype "passive"))
      (node (ref "X1") (pin "6") (pinfunction "S_6") (pintype "passive"))
    )
    (net (code "74") (name "HEATER_2_PWR_RTN") (class "Default")
      (node (ref "C3_CMD") (pin "11") (pinfunction "11_11") (pintype "passive"))
      (node (ref "Q5") (pin "C") (pinfunction "C_C") (pintype "passive"))
      (node (ref "X1") (pin "7") (pinfunction "S_7") (pintype "passive"))
    )
    (net (code "75") (name "HEATER_CONTROL_1") (class "Default")
      (node (ref "ARD_7") (pin "10") (pinfunction "10_10") (pintype "passive"))
      (node (ref "R10") (pin "2") (pinfunction "2_2") (pintype "passive"))
    )
    (net (code "76") (name "HEATER_CONTROL_2") (class "Default")
      (node (ref "ARD_6") (pin "3") (pinfunction "3_3") (pintype "passive"))
      (node (ref "R11") (pin "2") (pinfunction "2_2") (pintype "passive"))
    )
    (net (code "77") (name "IOREF") (class "Default")
      (node (ref "ARD_1") (pin "2") (pinfunction "2_2") (pintype "passive"))
    )
    (net (code "78") (name "LI_ION") (class "Default")
      (node (ref "RB2") (pin "7") (pinfunction "7_7") (pintype "passive"))
    )
    (net (code "79") (name "LOAD_IN") (class "Default")
      (node (ref "LCC") (pin "6") (pinfunction "6_6") (pintype "passive"))
      (node (ref "X2") (pin "9") (pinfunction "S_9") (pintype "passive"))
    )
    (net (code "80") (name "MISO") (class "Default")
      (node (ref "ARD_4") (pin "1") (pinfunction "1_1") (pintype "passive"))
      (node (ref "ARD_7") (pin "6") (pinfunction "6_6") (pintype "passive"))
    )
    (net (code "81") (name "MOSI") (class "Default")
      (node (ref "ARD_4") (pin "4") (pinfunction "4_4") (pintype "passive"))
      (node (ref "ARD_7") (pin "7") (pinfunction "7_7") (pintype "passive"))
    )
    (net (code "82") (name "NET_AV") (class "Default")
      (node (ref "RB2") (pin "5") (pinfunction "5_5") (pintype "passive"))
    )
    (net (code "83") (name "Net-(Q4-PadB)") (class "Default")
      (node (ref "Q4") (pin "B") (pinfunction "B_B") (pintype "passive"))
      (node (ref "R10") (pin "1") (pinfunction "1_1") (pintype "passive"))
      (node (ref "R12") (pin "2") (pinfunction "2_2") (pintype "passive"))
    )
    (net (code "84") (name "Net-(Q5-PadB)") (class "Default")
      (node (ref "Q5") (pin "B") (pinfunction "B_B") (pintype "passive"))
      (node (ref "R11") (pin "1") (pinfunction "1_1") (pintype "passive"))
      (node (ref "R13") (pin "2") (pinfunction "2_2") (pintype "passive"))
    )
    (net (code "85") (name "Net-(Q6-PadB)") (class "Default")
      (node (ref "Q6") (pin "B") (pinfunction "B_B") (pintype "passive"))
      (node (ref "R16") (pin "1") (pinfunction "1_1") (pintype "passive"))
      (node (ref "R18") (pin "2") (pinfunction "2_2") (pintype "passive"))
    )
    (net (code "86") (name "Net-(Q7-PadB)") (class "Default")
      (node (ref "Q7") (pin "B") (pinfunction "B_B") (pintype "passive"))
      (node (ref "R17") (pin "1") (pinfunction "1_1") (pintype "passive"))
      (node (ref "R19") (pin "2") (pinfunction "2_2") (pintype "passive"))
    )
    (net (code "87") (name "Net-(T1-B)") (class "Default")
      (node (ref "R1") (pin "1") (pinfunction "1_1") (pintype "passive"))
      (node (ref "R2") (pin "2") (pinfunction "2_2") (pintype "passive"))
      (node (ref "T1") (pin "2") (pinfunction "B_2") (pintype "passive"))
    )
    (net (code "88") (name "Net-(T1-E)") (class "Default")
      (node (ref "Q1") (pin "B") (pinfunction "B_B") (pintype "passive"))
      (node (ref "R2") (pin "1") (pinfunction "1_1") (pintype "passive"))
      (node (ref "R3") (pin "2") (pinfunction "2_2") (pintype "passive"))
      (node (ref "T1") (pin "3") (pinfunction "E_3") (pintype "passive"))
    )
    (net (code "89") (name "Net-(T2-B)") (class "Default")
      (node (ref "R4") (pin "1") (pinfunction "1_1") (pintype "passive"))
      (node (ref "R6") (pin "2") (pinfunction "2_2") (pintype "passive"))
      (node (ref "T2") (pin "2") (pinfunction "B_2") (pintype "passive"))
    )
    (net (code "90") (name "Net-(T2-E)") (class "Default")
      (node (ref "Q2") (pin "B") (pinfunction "B_B") (pintype "passive"))
      (node (ref "R6") (pin "1") (pinfunction "1_1") (pintype "passive"))
      (node (ref "R8") (pin "2") (pinfunction "2_2") (pintype "passive"))
      (node (ref "T2") (pin "3") (pinfunction "E_3") (pintype "passive"))
    )
    (net (code "91") (name "Net-(T3-B)") (class "Default")
      (node (ref "R5") (pin "1") (pinfunction "1_1") (pintype "passive"))
      (node (ref "R7") (pin "2") (pinfunction "2_2") (pintype "passive"))
      (node (ref "T3") (pin "2") (pinfunction "B_2") (pintype "passive"))
    )
    (net (code "92") (name "Net-(T3-E)") (class "Default")
      (node (ref "Q3") (pin "B") (pinfunction "B_B") (pintype "passive"))
      (node (ref "R7") (pin "1") (pinfunction "1_1") (pintype "passive"))
      (node (ref "R9") (pin "2") (pinfunction "2_2") (pintype "passive"))
      (node (ref "T3") (pin "3") (pinfunction "E_3") (pintype "passive"))
    )
    (net (code "93") (name "ON_OFF") (class "Default")
      (node (ref "RB2") (pin "6") (pinfunction "6_6") (pintype "passive"))
    )
    (net (code "94") (name "PYRO_1_PWR") (class "Default")
      (node (ref "C3_CMD") (pin "1") (pinfunction "1_1") (pintype "passive"))
      (node (ref "PO1") (pin "1") (pinfunction "P_1") (pintype "passive"))
    )
    (net (code "95") (name "PYRO_1_PWR_RTN") (class "Default")
      (node (ref "C3_CMD") (pin "2") (pinfunction "2_2") (pintype "passive"))
      (node (ref "Q1") (pin "C") (pinfunction "C_C") (pintype "passive"))
      (node (ref "T1") (pin "1") (pinfunction "C_1") (pintype "passive"))
    )
    (net (code "96") (name "PYRO_2_PWR") (class "Default")
      (node (ref "C3_CMD") (pin "3") (pinfunction "3_3") (pintype "passive"))
      (node (ref "PO2") (pin "1") (pinfunction "P_1") (pintype "passive"))
    )
    (net (code "97") (name "PYRO_2_PWR_RTN") (class "Default")
      (node (ref "C3_CMD") (pin "4") (pinfunction "4_4") (pintype "passive"))
      (node (ref "Q2") (pin "C") (pinfunction "C_C") (pintype "passive"))
      (node (ref "T2") (pin "1") (pinfunction "C_1") (pintype "passive"))
    )
    (net (code "98") (name "RESET") (class "Default")
      (node (ref "ARD_1") (pin "3") (pinfunction "3_3") (pintype "passive"))
      (node (ref "ARD_4") (pin "5") (pinfunction "5_5") (pintype "passive"))
    )
    (net (code "99") (name "RF_IN") (class "Default")
      (node (ref "GPS") (pin "2") (pinfunction "2_2") (pintype "passive"))
    )
    (net (code "100") (name "RI") (class "Default")
      (node (ref "RB2") (pin "4") (pinfunction "4_4") (pintype "passive"))
    )
    (net (code "101") (name "RTS") (class "Default")
      (node (ref "RB1") (pin "1") (pinfunction "1_1") (pintype "passive"))
    )
    (net (code "102") (name "RX0") (class "Default")
      (node (ref "ARD_6") (pin "8") (pinfunction "8_8") (pintype "passive"))
      (node (ref "X12") (pin "2") (pinfunction "D-_2") (pintype "bidirectional"))
    )
    (net (code "103") (name "RX1") (class "Default")
      (node (ref "ARD_5") (pin "6") (pinfunction "6_6") (pintype "passive"))
      (node (ref "GPS") (pin "5") (pinfunction "5_5") (pintype "passive"))
    )
    (net (code "104") (name "RX2") (class "Default")
      (node (ref "ARD_5") (pin "4") (pinfunction "4_4") (pintype "passive"))
    )
    (net (code "105") (name "RX3") (class "Default")
      (node (ref "ARD_5") (pin "2") (pinfunction "2_2") (pintype "passive"))
      (node (ref "RB1") (pin "2") (pinfunction "2_2") (pintype "passive"))
    )
    (net (code "106") (name "RXB") (class "Default")
      (node (ref "GPS") (pin "7") (pinfunction "7_7") (pintype "passive"))
    )
    (net (code "107") (name "SCK") (class "Default")
      (node (ref "ARD_4") (pin "3") (pinfunction "3_3") (pintype "passive"))
      (node (ref "ARD_7") (pin "5") (pinfunction "5_5") (pintype "passive"))
    )
    (net (code "108") (name "SCL") (class "Default")
      (node (ref "ARD_5") (pin "8") (pinfunction "8_8") (pintype "passive"))
      (node (ref "B1CC") (pin "3") (pinfunction "3_3") (pintype "passive"))
      (node (ref "B2CC") (pin "3") (pinfunction "3_3") (pintype "passive"))
      (node (ref "CN3") (pin "1") (pinfunction "1_1") (pintype "bidirectional"))
      (node (ref "LCC") (pin "3") (pinfunction "3_3") (pintype "passive"))
      (node (ref "SACC") (pin "3") (pinfunction "3_3") (pintype "passive"))
    )
    (net (code "109") (name "SCL1") (class "Default")
      (node (ref "ARD_7") (pin "1") (pinfunction "1_1") (pintype "passive"))
    )
    (net (code "110") (name "SDA") (class "Default")
      (node (ref "ARD_5") (pin "7") (pinfunction "7_7") (pintype "passive"))
      (node (ref "B1CC") (pin "4") (pinfunction "4_4") (pintype "passive"))
      (node (ref "B2CC") (pin "4") (pinfunction "4_4") (pintype "passive"))
      (node (ref "CN3") (pin "2") (pinfunction "2_2") (pintype "bidirectional"))
      (node (ref "LCC") (pin "4") (pinfunction "4_4") (pintype "passive"))
      (node (ref "SACC") (pin "4") (pinfunction "4_4") (pintype "passive"))
    )
    (net (code "111") (name "SDA1") (class "Default")
      (node (ref "ARD_7") (pin "2") (pinfunction "2_2") (pintype "passive"))
    )
    (net (code "112") (name "SPARE_1_PWR") (class "Default")
      (node (ref "C3_CMD") (pin "12") (pinfunction "12_12") (pintype "passive"))
      (node (ref "PO6") (pin "1") (pinfunction "P_1") (pintype "passive"))
      (node (ref "SPRL1") (pin "1") (pinfunction "S_1") (pintype "passive"))
    )
    (net (code "113") (name "SPARE_1_PWR_RTN") (class "Default")
      (node (ref "C3_CMD") (pin "13") (pinfunction "13_13") (pintype "passive"))
      (node (ref "Q6") (pin "C") (pinfunction "C_C") (pintype "passive"))
    )
    (net (code "114") (name "SPARE_HIGH_1_CONTROL") (class "Default")
      (node (ref "ARD_9") (pin "2") (pinfunction "2_2") (pintype "passive"))
      (node (ref "R5") (pin "2") (pinfunction "2_2") (pintype "passive"))
    )
    (net (code "115") (name "SPARE_HIGH_1_PWR") (class "Default")
      (node (ref "C3_CMD") (pin "5") (pinfunction "5_5") (pintype "passive"))
      (node (ref "PO3") (pin "1") (pinfunction "P_1") (pintype "passive"))
      (node (ref "SPRH1") (pin "1") (pinfunction "S_1") (pintype "passive"))
    )
    (net (code "116") (name "SPARE_HIGH_1_PWR_RTN") (class "Default")
      (node (ref "C3_CMD") (pin "6") (pinfunction "6_6") (pintype "passive"))
      (node (ref "Q3") (pin "C") (pinfunction "C_C") (pintype "passive"))
      (node (ref "T3") (pin "1") (pinfunction "C_1") (pintype "passive"))
    )
    (net (code "117") (name "SPARE_LOW_1_CONTROL") (class "Default")
      (node (ref "ARD_9") (pin "3") (pinfunction "3_3") (pintype "passive"))
      (node (ref "R16") (pin "2") (pinfunction "2_2") (pintype "passive"))
    )
    (net (code "118") (name "S{slash}A_PWR_IN") (class "Default")
      (node (ref "C2_PWR") (pin "10") (pinfunction "10_10") (pintype "passive"))
      (node (ref "C2_PWR") (pin "6") (pinfunction "6_6") (pintype "passive"))
      (node (ref "C2_PWR") (pin "8") (pinfunction "8_8") (pintype "passive"))
      (node (ref "SACC") (pin "6") (pinfunction "6_6") (pintype "passive"))
    )
    (net (code "119") (name "S{slash}A_PWR_OUT") (class "Default")
      (node (ref "SACC") (pin "5") (pinfunction "5_5") (pintype "passive"))
      (node (ref "X2") (pin "1") (pinfunction "S_1") (pintype "passive"))
    )
    (net (code "120") (name "S{slash}A_PWR_OUT_RTN") (class "Default")
      (node (ref "X2") (pin "2") (pinfunction "S_2") (pintype "passive"))
    )
    (net (code "121") (name "S{slash}A_PWR_RTN") (class "Default")
      (node (ref "C2_PWR") (pin "11") (pinfunction "11_11") (pintype "passive"))
      (node (ref "C2_PWR") (pin "7") (pinfunction "7_7") (pintype "passive"))
      (node (ref "C2_PWR") (pin "9") (pinfunction "9_9") (pintype "passive"))
    )
    (net (code "122") (name "TEMP_EXT_1") (class "Default")
      (node (ref "ARD_2") (pin "8") (pinfunction "8_8") (pintype "passive"))
      (node (ref "C1_TLM") (pin "1") (pinfunction "1_1") (pintype "passive"))
      (node (ref "R22") (pin "1") (pinfunction "1_1") (pintype "passive"))
      (node (ref "R23") (pin "2") (pinfunction "2_2") (pintype "passive"))
    )
    (net (code "123") (name "TEMP_EXT_2") (class "Default")
      (node (ref "ARD_2") (pin "6") (pinfunction "6_6") (pintype "passive"))
      (node (ref "C1_TLM") (pin "3") (pinfunction "3_3") (pintype "passive"))
      (node (ref "R24") (pin "1") (pinfunction "1_1") (pintype "passive"))
      (node (ref "R25") (pin "2") (pinfunction "2_2") (pintype "passive"))
    )
    (net (code "124") (name "TX0") (class "Default")
      (node (ref "ARD_6") (pin "7") (pinfunction "7_7") (pintype "passive"))
      (node (ref "X12") (pin "3") (pinfunction "D+_3") (pintype "bidirectional"))
    )
    (net (code "125") (name "TX1") (class "Default")
      (node (ref "ARD_5") (pin "5") (pinfunction "5_5") (pintype "passive"))
      (node (ref "GPS") (pin "4") (pinfunction "4_4") (pintype "passive"))
    )
    (net (code "126") (name "TX2") (class "Default")
      (node (ref "ARD_5") (pin "3") (pinfunction "3_3") (pintype "passive"))
    )
    (net (code "127") (name "TX3") (class "Default")
      (node (ref "ARD_5") (pin "1") (pinfunction "1_1") (pintype "passive"))
      (node (ref "RB1") (pin "3") (pinfunction "3_3") (pintype "passive"))
    )
    (net (code "128") (name "TXB") (class "Default")
      (node (ref "GPS") (pin "6") (pinfunction "6_6") (pintype "passive"))
    )
    (net (code "129") (name "UNKNOWN") (class "Default")
      (node (ref "ARD_1") (pin "1") (pinfunction "1_1") (pintype "passive"))
    )
    (net (code "130") (name "VBAT") (class "Default")
      (node (ref "GPS") (pin "3") (pinfunction "3_3") (pintype "passive"))
    )
    (net (code "131") (name "VCC_RB") (class "Default")
      (node (ref "RB1") (pin "4") (pinfunction "4_4") (pintype "passive"))
    )
    (net (code "132") (name "VIN") (class "Default")
      (node (ref "ARD_1") (pin "8") (pinfunction "8_8") (pintype "passive"))
      (node (ref "LCC") (pin "5") (pinfunction "5_5") (pintype "passive"))
      (node (ref "PVIN1") (pin "1") (pinfunction "P_1") (pintype "passive"))
      (node (ref "PVIN2") (pin "1") (pinfunction "P_1") (pintype "passive"))
      (node (ref "PVIN3") (pin "1") (pinfunction "P_1") (pintype "passive"))
      (node (ref "PVIN4") (pin "1") (pinfunction "P_1") (pintype "passive"))
      (node (ref "PVIN5") (pin "1") (pinfunction "P_1") (pintype "passive"))
      (node (ref "PVIN6") (pin "1") (pinfunction "P_1") (pintype "passive"))
      (node (ref "PVIN7") (pin "1") (pinfunction "P_1") (pintype "passive"))
      (node (ref "R14") (pin "2") (pinfunction "2_2") (pintype "passive"))
    )
    (net (code "133") (name "VIN_VOLTAGE_TLM") (class "Default")
      (node (ref "ARD_2") (pin "4") (pinfunction "4_4") (pintype "passive"))
      (node (ref "C1") (pin "1") (pinfunction "1_1") (pintype "passive"))
      (node (ref "R14") (pin "1") (pinfunction "1_1") (pintype "passive"))
      (node (ref "R15") (pin "2") (pinfunction "2_2") (pintype "passive"))
    )
    (net (code "134") (name "unconnected-(ALT-Pad8)") (class "Default")
      (node (ref "ALT") (pin "8") (pinfunction "8_8") (pintype "passive"))
    )
    (net (code "135") (name "unconnected-(C1_TLM-Pad5)") (class "Default")
      (node (ref "C1_TLM") (pin "5") (pinfunction "5_5") (pintype "passive"))
    )
    (net (code "136") (name "unconnected-(C2_PWR-Pad5)") (class "Default")
      (node (ref "C2_PWR") (pin "5") (pinfunction "5_5") (pintype "passive"))
    )
    (net (code "137") (name "unconnected-(C2_PWR-Pad12)") (class "Default")
      (node (ref "C2_PWR") (pin "12") (pinfunction "12_12") (pintype "passive"))
    )
    (net (code "138") (name "unconnected-(C2_PWR-Pad13)") (class "Default")
      (node (ref "C2_PWR") (pin "13") (pinfunction "13_13") (pintype "passive"))
    )
    (net (code "139") (name "unconnected-(C2_PWR-Pad14)") (class "Default")
      (node (ref "C2_PWR") (pin "14") (pinfunction "14_14") (pintype "passive"))
    )
    (net (code "140") (name "unconnected-(C2_PWR-Pad15)") (class "Default")
      (node (ref "C2_PWR") (pin "15") (pinfunction "15_15") (pintype "passive"))
    )
    (net (code "141") (name "unconnected-(C3_CMD-Pad7)") (class "Default")
      (node (ref "C3_CMD") (pin "7") (pinfunction "7_7") (pintype "passive"))
    )
    (net (code "142") (name "unconnected-(EEPROM1-A0-Pad1)") (class "Default")
      (node (ref "EEPROM1") (pin "1") (pinfunction "A0_1") (pintype "bidirectional"))
    )
    (net (code "143") (name "unconnected-(EEPROM1-A1-Pad2)") (class "Default")
      (node (ref "EEPROM1") (pin "2") (pinfunction "A1_2") (pintype "bidirectional"))
    )
    (net (code "144") (name "unconnected-(EEPROM1-A2-Pad3)") (class "Default")
      (node (ref "EEPROM1") (pin "3") (pinfunction "A2_3") (pintype "bidirectional"))
    )
    (net (code "145") (name "unconnected-(EEPROM1-WP-Pad7)") (class "Default")
      (node (ref "EEPROM1") (pin "7") (pinfunction "WP_7") (pintype "bidirectional"))
    )
  )
)
